# MAX30102_Heart-Rate_Sensor.net
KiCad netlist of a schematic drawn in Altium Designer
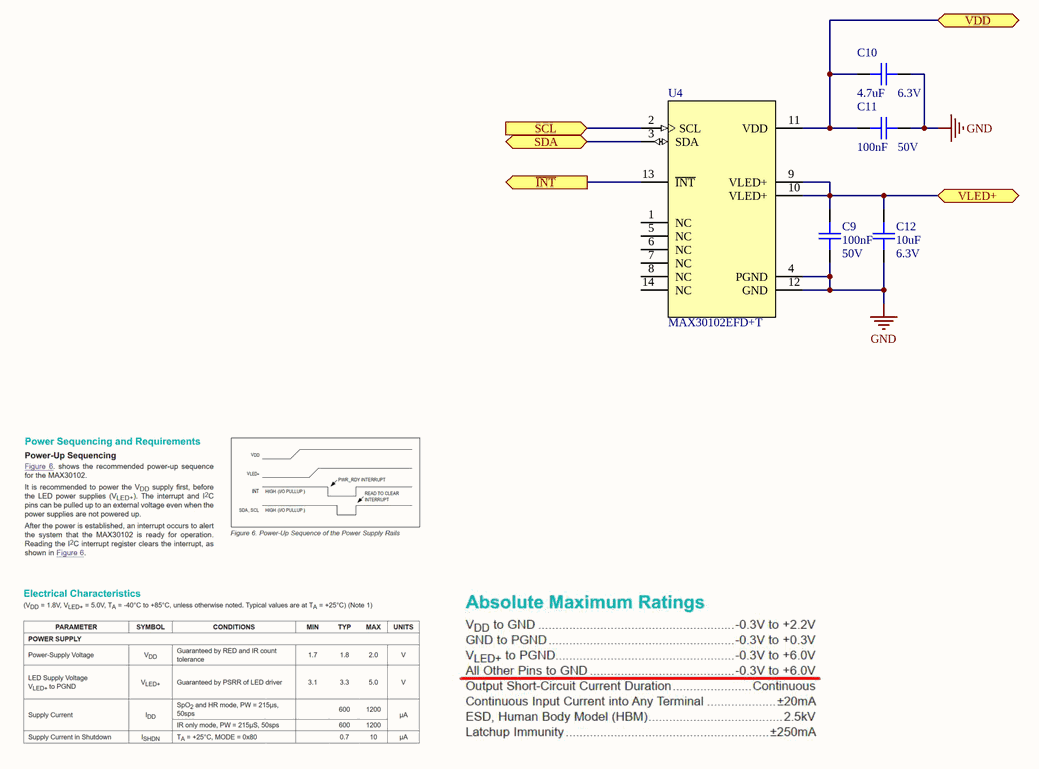
[diagram p0: MAX30102_Heart-Rate_Sensor.SchDoc]

(export (version "E")
  (design (tool "Eeschema 10.0.6"))
  (components
    (comp (ref "C9")
      (value "CAP CER 0.1UF 50V X7R 0402")
      (footprint "C0402")
      (description "0.1µF ±10% 50V Ceramic Capacitor X7R 0402 (1005 Metric)")
      (fields
        (field (name "MANUFACTURER") "TDK")
        (field (name "MANUFACTURER PART NUMBER") "CGA2B3X7R1H104K050BB")
        (field (name "CAPACITANCE") "100nF")
        (field (name "VOLTAGE") "50V")
      )
      (libsource (lib "capacitors_smd") (part "CAP CER 0.1UF 50V X7R 0402"))
    )
    (comp (ref "C10")
      (value "CAP CER 4.7UF 6.3V X5R 0402")
      (footprint "C0402")
      (description "4.7µF ±20% 6.3V Ceramic Capacitor X5R 0402 (1005 Metric)")
      (fields
        (field (name "MANUFACTURER") "Samsung")
        (field (name "MANUFACTURER PART NUMBER") "CL05A475MQ5NRNC")
        (field (name "CAPACITANCE") "4.7uF")
        (field (name "VOLTAGE RATING") "6.3V")
      )
      (libsource (lib "capacitors_smd") (part "CAP CER 4.7UF 6.3V X5R 0402"))
    )
    (comp (ref "C11")
      (value "CAP CER 0.1UF 50V X7R 0402")
      (footprint "C0402")
      (description "0.1µF ±10% 50V Ceramic Capacitor X7R 0402 (1005 Metric)")
      (fields
        (field (name "MANUFACTURER") "TDK")
        (field (name "MANUFACTURER PART NUMBER") "CGA2B3X7R1H104K050BB")
        (field (name "CAPACITANCE") "100nF")
        (field (name "VOLTAGE") "50V")
      )
      (libsource (lib "capacitors_smd") (part "CAP CER 0.1UF 50V X7R 0402"))
    )
    (comp (ref "C12")
      (value "CAP CER 10UF 6.3V X5R 0402")
      (footprint "C0402")
      (description "10µF ±20% 6.3V Ceramic Capacitor X5R 0402 (1005 Metric)")
      (fields
        (field (name "MANUFACTURER") "Samsung")
        (field (name "MANUFACTURER PART NUMBER") "CL05A106MQ5NUNC")
        (field (name "CAPACITANCE") "10uF")
        (field (name "VOLTAGE RATING") "6.3V")
      )
      (libsource (lib "capacitors_smd") (part "CAP CER 10UF 6.3V X5R 0402"))
    )
    (comp (ref "U4")
      (value "MAX30102EFD+T")
      (footprint "XDCR_MAX30101EFD+")
      (description "Oximeter/Heart Rate Sensor IÂ²C Output")
      (fields (field (name "MANUFACTURER") "Maxim"))
      (libsource (lib "BLDC_Motor_Driver") (part "IC MAX30102EFD+T INTEGRATED OPTICAL SENSOR"))
    )
  )
  (nets
    (net (code "1") (name "/INT") (class "Default")
      (node (ref "U4") (pin "13") (pinfunction "INT_13") (pintype "open_collector"))
    )
    (net (code "2") (name "/SCL") (class "Default")
      (node (ref "U4") (pin "2") (pinfunction "SCL_2") (pintype "input"))
    )
    (net (code "3") (name "/SDA") (class "Default")
      (node (ref "U4") (pin "3") (pinfunction "SDA_3") (pintype "bidirectional"))
    )
    (net (code "4") (name "/VDD") (class "Default")
      (node (ref "C10") (pin "1") (pinfunction "1_1") (pintype "passive"))
      (node (ref "C11") (pin "1") (pinfunction "1_1") (pintype "passive"))
      (node (ref "U4") (pin "11") (pinfunction "VDD_11") (pintype "power_in"))
    )
    (net (code "5") (name "/VLED+") (class "Default")
      (node (ref "C12") (pin "2") (pinfunction "2_2") (pintype "passive"))
      (node (ref "C9") (pin "2") (pinfunction "2_2") (pintype "passive"))
      (node (ref "U4") (pin "10") (pinfunction "VLED+_10") (pintype "power_in"))
      (node (ref "U4") (pin "9") (pinfunction "VLED+_9") (pintype "power_in"))
    )
    (net (code "6") (name "GND") (class "Default")
      (node (ref "C10") (pin "2") (pinfunction "2_2") (pintype "passive"))
      (node (ref "C11") (pin "2") (pinfunction "2_2") (pintype "passive"))
      (node (ref "C12") (pin "1") (pinfunction "1_1") (pintype "passive"))
      (node (ref "C9") (pin "1") (pinfunction "1_1") (pintype "passive"))
      (node (ref "U4") (pin "12") (pinfunction "GND_12") (pintype "power_in"))
      (node (ref "U4") (pin "4") (pinfunction "PGND_4") (pintype "power_in"))
    )
    (net (code "7") (name "unconnected-(U4-NC-Pad1)") (class "Default")
      (node (ref "U4") (pin "1") (pinfunction "NC_1") (pintype "passive"))
    )
    (net (code "8") (name "unconnected-(U4-NC-Pad5)") (class "Default")
      (node (ref "U4") (pin "5") (pinfunction "NC_5") (pintype "passive"))
    )
    (net (code "9") (name "unconnected-(U4-NC-Pad6)") (class "Default")
      (node (ref "U4") (pin "6") (pinfunction "NC_6") (pintype "passive"))
    )
    (net (code "10") (name "unconnected-(U4-NC-Pad7)") (class "Default")
      (node (ref "U4") (pin "7") (pinfunction "NC_7") (pintype "passive"))
    )
    (net (code "11") (name "unconnected-(U4-NC-Pad8)") (class "Default")
      (node (ref "U4") (pin "8") (pinfunction "NC_8") (pintype "passive"))
    )
    (net (code "12") (name "unconnected-(U4-NC-Pad14)") (class "Default")
      (node (ref "U4") (pin "14") (pinfunction "NC_14") (pintype "passive"))
    )
  )
)
